# transistor.net
KiCad netlist of a schematic drawn in EAGLE
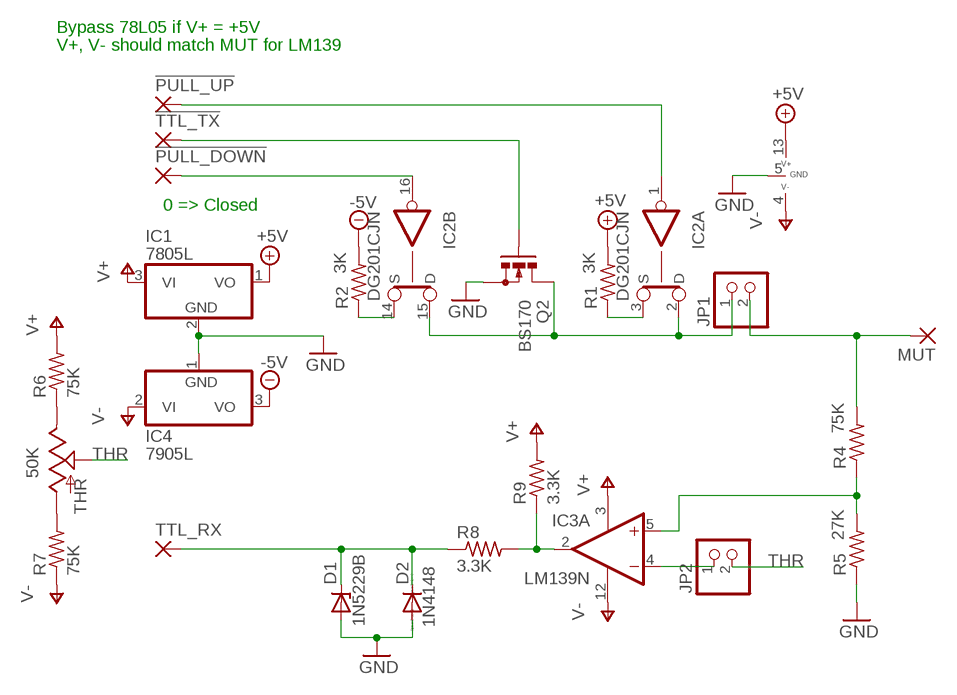
[diagram p0: schematic, sheet 1]

(export (version "E")
  (design (tool "Eeschema 10.0.6"))
  (components
    (comp (ref "!PULL_DOWN")
      (value "1,6/0,9")
      (footprint "eagle-import:1,6_0,9")
      (libsource (lib "eagle-import") (part "1,6/0,9"))
    )
    (comp (ref "!PULL_UP")
      (value "1,6/0,9")
      (footprint "eagle-import:1,6_0,9")
      (libsource (lib "eagle-import") (part "1,6/0,9"))
    )
    (comp (ref "!TTL_TX")
      (value "1,6/0,9")
      (footprint "eagle-import:1,6_0,9")
      (libsource (lib "eagle-import") (part "1,6/0,9"))
    )
    (comp (ref "D1")
      (value "1N5229B")
      (footprint "eagle-import:DO35Z10")
      (libsource (lib "eagle-import") (part "ZENER-DIODEDO35Z10"))
    )
    (comp (ref "D2")
      (value "1N4148")
      (footprint "eagle-import:DO35-10")
      (libsource (lib "eagle-import") (part "1N4148DO35-10"))
    )
    (comp (ref "IC1")
      (value "7805L")
      (footprint "eagle-import:TO92")
      (libsource (lib "eagle-import") (part "78L05"))
    )
    (comp (ref "IC2")
      (value "DG201CJN")
      (footprint "eagle-import:DIL16")
      (libsource (lib "eagle-import") (part "DG201CJN"))
    )
    (comp (ref "IC3")
      (value "LM139N")
      (footprint "eagle-import:DIL14")
      (libsource (lib "eagle-import") (part "LM339N"))
    )
    (comp (ref "IC4")
      (value "7905L")
      (footprint "eagle-import:TO92")
      (libsource (lib "eagle-import") (part "79L05"))
    )
    (comp (ref "JP1")
      (value "PINHD-1X2")
      (footprint "eagle-import:1X02")
      (libsource (lib "eagle-import") (part "PINHD-1X2"))
    )
    (comp (ref "JP2")
      (value "PINHD-1X2")
      (footprint "eagle-import:1X02")
      (libsource (lib "eagle-import") (part "PINHD-1X2"))
    )
    (comp (ref "MUT")
      (value "1,6/0,9")
      (footprint "eagle-import:1,6_0,9")
      (libsource (lib "eagle-import") (part "1,6/0,9"))
    )
    (comp (ref "Q2")
      (value "BS170")
      (footprint "eagle-import:SOT54E")
      (libsource (lib "eagle-import") (part "BS170"))
    )
    (comp (ref "R1")
      (value "3K")
      (footprint "eagle-import:0207_10")
      (libsource (lib "eagle-import") (part "R-US_0207/10"))
    )
    (comp (ref "R2")
      (value "3K")
      (footprint "eagle-import:0207_10")
      (libsource (lib "eagle-import") (part "R-US_0207/10"))
    )
    (comp (ref "R4")
      (value "75K")
      (footprint "eagle-import:0207_10")
      (libsource (lib "eagle-import") (part "R-US_0207/10"))
    )
    (comp (ref "R5")
      (value "27K")
      (footprint "eagle-import:0207_10")
      (libsource (lib "eagle-import") (part "R-US_0207/10"))
    )
    (comp (ref "R6")
      (value "75K")
      (footprint "eagle-import:0207_10")
      (libsource (lib "eagle-import") (part "R-US_0207/10"))
    )
    (comp (ref "R7")
      (value "75K")
      (footprint "eagle-import:0207_10")
      (libsource (lib "eagle-import") (part "R-US_0207/10"))
    )
    (comp (ref "R8")
      (value "3.3K")
      (footprint "eagle-import:0207_10")
      (libsource (lib "eagle-import") (part "R-US_0207/10"))
    )
    (comp (ref "R9")
      (value "3.3K")
      (footprint "eagle-import:0207_10")
      (libsource (lib "eagle-import") (part "R-US_0207/10"))
    )
    (comp (ref "THR")
      (value "50K")
      (footprint "eagle-import:SP19L")
      (libsource (lib "eagle-import") (part "TRIM_US-S43P"))
    )
    (comp (ref "TTL_RX")
      (value "1,6/0,9")
      (footprint "eagle-import:1,6_0,9")
      (libsource (lib "eagle-import") (part "1,6/0,9"))
    )
  )
  (nets
    (net (code "1") (name "+5V") (class "Default")
      (node (ref "IC1") (pin "1") (pinfunction "VO_1") (pintype "passive"))
      (node (ref "IC2") (pin "13") (pinfunction "V+_13") (pintype "power_in"))
      (node (ref "R1") (pin "2") (pinfunction "2_2") (pintype "passive"))
    )
    (net (code "2") (name "-5V") (class "Default")
      (node (ref "IC4") (pin "3") (pinfunction "VO_3") (pintype "passive"))
      (node (ref "R2") (pin "2") (pinfunction "2_2") (pintype "passive"))
    )
    (net (code "3") (name "/THR") (class "Default")
      (node (ref "JP2") (pin "2") (pinfunction "2_2") (pintype "passive"))
      (node (ref "THR") (pin "S") (pinfunction "S_S") (pintype "passive"))
    )
    (net (code "4") (name "GND") (class "Default")
      (node (ref "D1") (pin "A") (pinfunction "A_A") (pintype "passive"))
      (node (ref "D2") (pin "A") (pinfunction "A_A") (pintype "passive"))
      (node (ref "IC1") (pin "2") (pinfunction "GND_2") (pintype "passive"))
      (node (ref "IC2") (pin "5") (pinfunction "GND_5") (pintype "power_in"))
      (node (ref "IC4") (pin "1") (pinfunction "GND_1") (pintype "passive"))
      (node (ref "Q2") (pin "S") (pinfunction "S_S") (pintype "passive"))
      (node (ref "R5") (pin "1") (pinfunction "1_1") (pintype "passive"))
    )
    (net (code "5") (name "Net-(!PULL_DOWN-P)") (class "Default")
      (node (ref "!PULL_DOWN") (pin "1") (pinfunction "P_1") (pintype "passive"))
      (node (ref "IC2") (pin "16") (pinfunction "IN_16") (pintype "input"))
    )
    (net (code "6") (name "Net-(!PULL_UP-P)") (class "Default")
      (node (ref "!PULL_UP") (pin "1") (pinfunction "P_1") (pintype "passive"))
      (node (ref "IC2") (pin "1") (pinfunction "IN_1") (pintype "input"))
    )
    (net (code "7") (name "Net-(!TTL_TX-P)") (class "Default")
      (node (ref "!TTL_TX") (pin "1") (pinfunction "P_1") (pintype "passive"))
      (node (ref "Q2") (pin "G") (pinfunction "G_G") (pintype "passive"))
    )
    (net (code "8") (name "Net-(IC2A-D)") (class "Default")
      (node (ref "IC2") (pin "15") (pinfunction "D_15") (pintype "bidirectional"))
      (node (ref "IC2") (pin "2") (pinfunction "D_2") (pintype "bidirectional"))
      (node (ref "JP1") (pin "1") (pinfunction "1_1") (pintype "passive"))
      (node (ref "Q2") (pin "D") (pinfunction "D_D") (pintype "passive"))
    )
    (net (code "9") (name "Net-(IC2A-S)") (class "Default")
      (node (ref "IC2") (pin "3") (pinfunction "S_3") (pintype "bidirectional"))
      (node (ref "R1") (pin "1") (pinfunction "1_1") (pintype "passive"))
    )
    (net (code "10") (name "Net-(IC2B-S)") (class "Default")
      (node (ref "IC2") (pin "14") (pinfunction "S_14") (pintype "bidirectional"))
      (node (ref "R2") (pin "1") (pinfunction "1_1") (pintype "passive"))
    )
    (net (code "11") (name "Net-(IC3A-+IN)") (class "Default")
      (node (ref "IC3") (pin "5") (pinfunction "+IN_5") (pintype "input"))
      (node (ref "R4") (pin "1") (pinfunction "1_1") (pintype "passive"))
      (node (ref "R5") (pin "2") (pinfunction "2_2") (pintype "passive"))
    )
    (net (code "12") (name "Net-(IC3A--IN)") (class "Default")
      (node (ref "IC3") (pin "4") (pinfunction "-IN_4") (pintype "input"))
      (node (ref "JP2") (pin "1") (pinfunction "1_1") (pintype "passive"))
    )
    (net (code "13") (name "Net-(IC3A-OUT)") (class "Default")
      (node (ref "IC3") (pin "2") (pinfunction "OUT_2") (pintype "open_collector"))
      (node (ref "R8") (pin "2") (pinfunction "2_2") (pintype "passive"))
      (node (ref "R9") (pin "1") (pinfunction "1_1") (pintype "passive"))
    )
    (net (code "14") (name "Net-(MUT-P)") (class "Default")
      (node (ref "JP1") (pin "2") (pinfunction "2_2") (pintype "passive"))
      (node (ref "MUT") (pin "1") (pinfunction "P_1") (pintype "passive"))
      (node (ref "R4") (pin "2") (pinfunction "2_2") (pintype "passive"))
    )
    (net (code "15") (name "Net-(R6-Pad1)") (class "Default")
      (node (ref "R6") (pin "1") (pinfunction "1_1") (pintype "passive"))
      (node (ref "THR") (pin "E") (pinfunction "E_E") (pintype "passive"))
    )
    (net (code "16") (name "Net-(R7-Pad2)") (class "Default")
      (node (ref "R7") (pin "2") (pinfunction "2_2") (pintype "passive"))
      (node (ref "THR") (pin "A") (pinfunction "A_A") (pintype "passive"))
    )
    (net (code "17") (name "Net-(TTL_RX-P)") (class "Default")
      (node (ref "D1") (pin "C") (pinfunction "C_C") (pintype "passive"))
      (node (ref "D2") (pin "C") (pinfunction "C_C") (pintype "passive"))
      (node (ref "R8") (pin "1") (pinfunction "1_1") (pintype "passive"))
      (node (ref "TTL_RX") (pin "1") (pinfunction "P_1") (pintype "passive"))
    )
    (net (code "18") (name "V+") (class "Default")
      (node (ref "IC1") (pin "3") (pinfunction "VI_3") (pintype "input"))
      (node (ref "IC3") (pin "3") (pinfunction "V+_3") (pintype "power_in"))
      (node (ref "R6") (pin "2") (pinfunction "2_2") (pintype "passive"))
      (node (ref "R9") (pin "2") (pinfunction "2_2") (pintype "passive"))
    )
    (net (code "19") (name "V-") (class "Default")
      (node (ref "IC2") (pin "4") (pinfunction "V-_4") (pintype "power_in"))
      (node (ref "IC3") (pin "12") (pinfunction "GND_12") (pintype "power_in"))
      (node (ref "IC4") (pin "2") (pinfunction "VI_2") (pintype "input"))
      (node (ref "R7") (pin "1") (pinfunction "1_1") (pintype "passive"))
    )
  )
)
